# ZYNQ_PW.net
KiCad netlist of a schematic drawn in Altium Designer
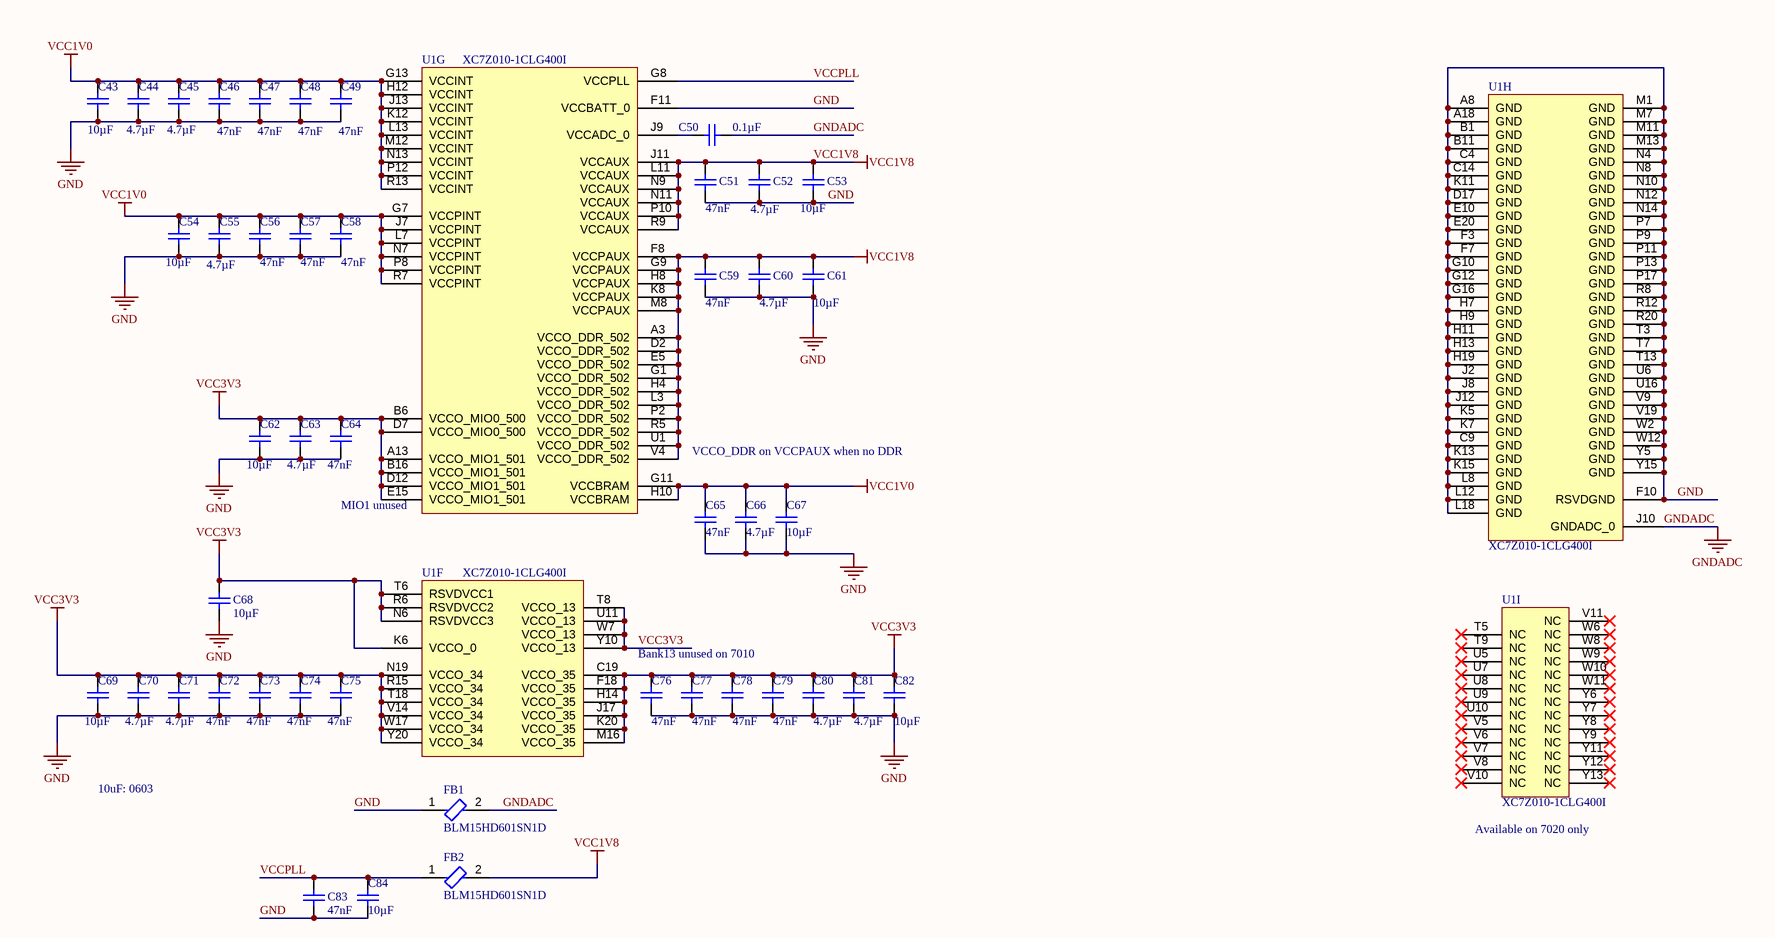
[diagram p0: ZYNQ_PW.SchDoc]

(export (version "E")
  (design (tool "Eeschema 10.0.6"))
  (components
    (comp (ref "C43")
      (value "10µF")
      (footprint "CAP0805i")
      (description "0805, 10uF, 10%, 25V, X7S")
      (fields
        (field (name "PART NUMBER") "GRT21BC71E106KE13L")
        (field (name "VOLTAGE") "25V")
        (field (name "CAPACITANCE") "10µF")
      )
      (libsource (lib "AmpherLib") (part "Cap_10uF_50V_X7S_0805"))
    )
    (comp (ref "C44")
      (value "4.7µF")
      (footprint "CAP0402i")
      (description "CAP CER 4.7UF 10V X5R 0402")
      (fields (field (name "PART NUMBER") "C1005X5R1A475K050BC") (field (name "TOLERANCE") "10%"))
      (libsource (lib "AmpherLib") (part "Cap_4.7uF_10V_10%_0402"))
    )
    (comp (ref "C45")
      (value "4.7µF")
      (footprint "CAP0402i")
      (description "CAP CER 4.7UF 10V X5R 0402")
      (fields
        (field (name "PART NUMBER") "C1005X5R1A475K050BC")
        (field (name "CAPACITANCE") "4.7µF")
        (field (name "TOLERANCE") "10%")
      )
      (libsource (lib "AmpherLib") (part "Cap_4.7uF_10V_10%_0402"))
    )
    (comp (ref "C46")
      (value "~")
      (footprint "CAP0201i")
      (description "0201, 47nF, 10%, 25V, X7R")
      (fields (field (name "CAPACITANCE") "47nF"))
      (libsource (lib "AmpherLib") (part "Cap_47nF_X7R_0201"))
    )
    (comp (ref "C47")
      (value "~")
      (footprint "CAP0201i")
      (description "0201, 47nF, 10%, 25V, X7R")
      (fields (field (name "CAPACITANCE") "47nF"))
      (libsource (lib "AmpherLib") (part "Cap_47nF_X7R_0201"))
    )
    (comp (ref "C48")
      (value "~")
      (footprint "CAP0201i")
      (description "0201, 47nF, 10%, 25V, X7R")
      (fields (field (name "CAPACITANCE") "47nF"))
      (libsource (lib "AmpherLib") (part "Cap_47nF_X7R_0201"))
    )
    (comp (ref "C49")
      (value "~")
      (footprint "CAP0201i")
      (description "0201, 47nF, 10%, 25V, X7R")
      (fields (field (name "CAPACITANCE") "47nF"))
      (libsource (lib "AmpherLib") (part "Cap_47nF_X7R_0201"))
    )
    (comp (ref "C50")
      (value "0.1µF")
      (footprint "CAP0402i")
      (description "0402, 0.1uF, 10%,  50V, X7R")
      (fields
        (field (name "PART NUMBER") "C1005X7R1H104K050BE")
        (field (name "VOLTAGE") "50V")
        (field (name "CAPACITANCE") "0.1µF")
      )
      (libsource (lib "AmpherLib") (part "Cap_0.1uF_50V_X7R_0402"))
    )
    (comp (ref "C51")
      (value "~")
      (footprint "CAP0201i")
      (description "0201, 47nF, 10%, 25V, X7R")
      (fields (field (name "CAPACITANCE") "47nF"))
      (libsource (lib "AmpherLib") (part "Cap_47nF_X7R_0201"))
    )
    (comp (ref "C52")
      (value "4.7µF")
      (footprint "CAP0402i")
      (description "CAP CER 4.7UF 10V X5R 0402")
      (fields
        (field (name "PART NUMBER") "C1005X5R1A475K050BC")
        (field (name "CAPACITANCE") "4.7µF")
        (field (name "TOLERANCE") "10%")
      )
      (libsource (lib "AmpherLib") (part "Cap_4.7uF_10V_10%_0402"))
    )
    (comp (ref "C53")
      (value "10µF")
      (footprint "CAP0805i")
      (description "0805, 10uF, 10%, 25V, X7S")
      (fields
        (field (name "PART NUMBER") "GRT21BC71E106KE13L")
        (field (name "VOLTAGE") "25V")
        (field (name "CAPACITANCE") "10µF")
      )
      (libsource (lib "AmpherLib") (part "Cap_10uF_50V_X7S_0805"))
    )
    (comp (ref "C54")
      (value "10µF")
      (footprint "CAP0805i")
      (description "0805, 10uF, 10%, 25V, X7S")
      (fields
        (field (name "PART NUMBER") "GRT21BC71E106KE13L")
        (field (name "VOLTAGE") "25V")
        (field (name "CAPACITANCE") "10µF")
      )
      (libsource (lib "AmpherLib") (part "Cap_10uF_50V_X7S_0805"))
    )
    (comp (ref "C55")
      (value "4.7µF")
      (footprint "CAP0402i")
      (description "CAP CER 4.7UF 10V X5R 0402")
      (fields
        (field (name "PART NUMBER") "C1005X5R1A475K050BC")
        (field (name "CAPACITANCE") "4.7µF")
        (field (name "TOLERANCE") "10%")
      )
      (libsource (lib "AmpherLib") (part "Cap_4.7uF_10V_10%_0402"))
    )
    (comp (ref "C56")
      (value "~")
      (footprint "CAP0201i")
      (description "0201, 47nF, 10%, 25V, X7R")
      (fields (field (name "CAPACITANCE") "47nF"))
      (libsource (lib "AmpherLib") (part "Cap_47nF_X7R_0201"))
    )
    (comp (ref "C57")
      (value "~")
      (footprint "CAP0201i")
      (description "0201, 47nF, 10%, 25V, X7R")
      (fields (field (name "CAPACITANCE") "47nF"))
      (libsource (lib "AmpherLib") (part "Cap_47nF_X7R_0201"))
    )
    (comp (ref "C58")
      (value "~")
      (footprint "CAP0201i")
      (description "0201, 47nF, 10%, 25V, X7R")
      (fields (field (name "CAPACITANCE") "47nF"))
      (libsource (lib "AmpherLib") (part "Cap_47nF_X7R_0201"))
    )
    (comp (ref "C59")
      (value "~")
      (footprint "CAP0201i")
      (description "0201, 47nF, 10%, 25V, X7R")
      (fields (field (name "CAPACITANCE") "47nF"))
      (libsource (lib "AmpherLib") (part "Cap_47nF_X7R_0201"))
    )
    (comp (ref "C60")
      (value "4.7µF")
      (footprint "CAP0402i")
      (description "CAP CER 4.7UF 10V X5R 0402")
      (fields
        (field (name "PART NUMBER") "C1005X5R1A475K050BC")
        (field (name "CAPACITANCE") "4.7µF")
        (field (name "TOLERANCE") "10%")
      )
      (libsource (lib "AmpherLib") (part "Cap_4.7uF_10V_10%_0402"))
    )
    (comp (ref "C61")
      (value "10µF")
      (footprint "CAP0805i")
      (description "0805, 10uF, 10%, 25V, X7S")
      (fields
        (field (name "PART NUMBER") "GRT21BC71E106KE13L")
        (field (name "VOLTAGE") "25V")
        (field (name "CAPACITANCE") "10µF")
      )
      (libsource (lib "AmpherLib") (part "Cap_10uF_50V_X7S_0805"))
    )
    (comp (ref "C62")
      (value "10µF")
      (footprint "CAP0805i")
      (description "0805, 10uF, 10%, 25V, X7S")
      (fields
        (field (name "PART NUMBER") "GRT21BC71E106KE13L")
        (field (name "VOLTAGE") "25V")
        (field (name "CAPACITANCE") "10µF")
      )
      (libsource (lib "AmpherLib") (part "Cap_10uF_50V_X7S_0805"))
    )
    (comp (ref "C63")
      (value "4.7µF")
      (footprint "CAP0402i")
      (description "CAP CER 4.7UF 10V X5R 0402")
      (fields (field (name "PART NUMBER") "C1005X5R1A475K050BC") (field (name "TOLERANCE") "10%"))
      (libsource (lib "AmpherLib") (part "Cap_4.7uF_10V_10%_0402"))
    )
    (comp (ref "C64")
      (value "~")
      (footprint "CAP0201i")
      (description "0201, 47nF, 10%, 25V, X7R")
      (fields (field (name "CAPACITANCE") "47nF"))
      (libsource (lib "AmpherLib") (part "Cap_47nF_X7R_0201"))
    )
    (comp (ref "C65")
      (value "~")
      (footprint "CAP0201i")
      (description "0201, 47nF, 10%, 25V, X7R")
      (fields (field (name "CAPACITANCE") "47nF"))
      (libsource (lib "AmpherLib") (part "Cap_47nF_X7R_0201"))
    )
    (comp (ref "C66")
      (value "4.7µF")
      (footprint "CAP0402i")
      (description "CAP CER 4.7UF 10V X5R 0402")
      (fields
        (field (name "PART NUMBER") "C1005X5R1A475K050BC")
        (field (name "CAPACITANCE") "4.7µF")
        (field (name "TOLERANCE") "10%")
      )
      (libsource (lib "AmpherLib") (part "Cap_4.7uF_10V_10%_0402"))
    )
    (comp (ref "C67")
      (value "10µF")
      (footprint "CAP0805i")
      (description "0805, 10uF, 10%, 25V, X7S")
      (fields (field (name "PART NUMBER") "GRT21BC71E106KE13L") (field (name "VOLTAGE") "25V"))
      (libsource (lib "AmpherLib") (part "Cap_10uF_50V_X7S_0805"))
    )
    (comp (ref "C68")
      (value "10µF")
      (footprint "CAP0805i")
      (description "0805, 10uF, 10%, 25V, X7S")
      (fields (field (name "PART NUMBER") "GRT21BC71E106KE13L") (field (name "VOLTAGE") "25V"))
      (libsource (lib "AmpherLib") (part "Cap_10uF_50V_X7S_0805"))
    )
    (comp (ref "C69")
      (value "10µF")
      (footprint "CAP0805i")
      (description "0805, 10uF, 10%, 25V, X7S")
      (fields (field (name "PART NUMBER") "GRT21BC71E106KE13L") (field (name "VOLTAGE") "25V"))
      (libsource (lib "AmpherLib") (part "Cap_10uF_50V_X7S_0805"))
    )
    (comp (ref "C70")
      (value "4.7µF")
      (footprint "CAP0402i")
      (description "CAP CER 4.7UF 10V X5R 0402")
      (fields
        (field (name "PART NUMBER") "C1005X5R1A475K050BC")
        (field (name "CAPACITANCE") "4.7µF")
        (field (name "TOLERANCE") "10%")
      )
      (libsource (lib "AmpherLib") (part "Cap_4.7uF_10V_10%_0402"))
    )
    (comp (ref "C71")
      (value "4.7µF")
      (footprint "CAP0402i")
      (description "CAP CER 4.7UF 10V X5R 0402")
      (fields
        (field (name "PART NUMBER") "C1005X5R1A475K050BC")
        (field (name "CAPACITANCE") "4.7µF")
        (field (name "TOLERANCE") "10%")
      )
      (libsource (lib "AmpherLib") (part "Cap_4.7uF_10V_10%_0402"))
    )
    (comp (ref "C72")
      (value "~")
      (footprint "CAP0201i")
      (description "0201, 47nF, 10%, 25V, X7R")
      (fields (field (name "CAPACITANCE") "47nF"))
      (libsource (lib "AmpherLib") (part "Cap_47nF_X7R_0201"))
    )
    (comp (ref "C73")
      (value "~")
      (footprint "CAP0201i")
      (description "0201, 47nF, 10%, 25V, X7R")
      (fields (field (name "CAPACITANCE") "47nF"))
      (libsource (lib "AmpherLib") (part "Cap_47nF_X7R_0201"))
    )
    (comp (ref "C74")
      (value "~")
      (footprint "CAP0201i")
      (description "0201, 47nF, 10%, 25V, X7R")
      (fields (field (name "CAPACITANCE") "47nF"))
      (libsource (lib "AmpherLib") (part "Cap_47nF_X7R_0201"))
    )
    (comp (ref "C75")
      (value "~")
      (footprint "CAP0201i")
      (description "0201, 47nF, 10%, 25V, X7R")
      (fields (field (name "CAPACITANCE") "47nF"))
      (libsource (lib "AmpherLib") (part "Cap_47nF_X7R_0201"))
    )
    (comp (ref "C76")
      (value "~")
      (footprint "CAP0201i")
      (description "0201, 47nF, 10%, 25V, X7R")
      (fields (field (name "CAPACITANCE") "47nF"))
      (libsource (lib "AmpherLib") (part "Cap_47nF_X7R_0201"))
    )
    (comp (ref "C77")
      (value "~")
      (footprint "CAP0201i")
      (description "0201, 47nF, 10%, 25V, X7R")
      (fields (field (name "CAPACITANCE") "47nF"))
      (libsource (lib "AmpherLib") (part "Cap_47nF_X7R_0201"))
    )
    (comp (ref "C78")
      (value "~")
      (footprint "CAP0201i")
      (description "0201, 47nF, 10%, 25V, X7R")
      (fields (field (name "CAPACITANCE") "47nF"))
      (libsource (lib "AmpherLib") (part "Cap_47nF_X7R_0201"))
    )
    (comp (ref "C79")
      (value "~")
      (footprint "CAP0201i")
      (description "0201, 47nF, 10%, 25V, X7R")
      (fields (field (name "CAPACITANCE") "47nF"))
      (libsource (lib "AmpherLib") (part "Cap_47nF_X7R_0201"))
    )
    (comp (ref "C80")
      (value "4.7µF")
      (footprint "CAP0402i")
      (description "CAP CER 4.7UF 10V X5R 0402")
      (fields
        (field (name "PART NUMBER") "C1005X5R1A475K050BC")
        (field (name "CAPACITANCE") "4.7µF")
        (field (name "TOLERANCE") "10%")
      )
      (libsource (lib "AmpherLib") (part "Cap_4.7uF_10V_10%_0402"))
    )
    (comp (ref "C81")
      (value "4.7µF")
      (footprint "CAP0402i")
      (description "CAP CER 4.7UF 10V X5R 0402")
      (fields (field (name "PART NUMBER") "C1005X5R1A475K050BC") (field (name "TOLERANCE") "10%"))
      (libsource (lib "AmpherLib") (part "Cap_4.7uF_10V_10%_0402"))
    )
    (comp (ref "C82")
      (value "10µF")
      (footprint "CAP0805i")
      (description "0805, 10uF, 10%, 25V, X7S")
      (fields (field (name "PART NUMBER") "GRT21BC71E106KE13L") (field (name "VOLTAGE") "25V"))
      (libsource (lib "AmpherLib") (part "Cap_10uF_50V_X7S_0805"))
    )
    (comp (ref "C83")
      (value "~")
      (footprint "CAP0201i")
      (description "0201, 47nF, 10%, 25V, X7R")
      (fields (field (name "CAPACITANCE") "47nF"))
      (libsource (lib "AmpherLib") (part "Cap_47nF_X7R_0201"))
    )
    (comp (ref "C84")
      (value "10µF")
      (footprint "CAP0805i")
      (description "0805, 10uF, 10%, 25V, X7S")
      (fields (field (name "PART NUMBER") "GRT21BC71E106KE13L") (field (name "VOLTAGE") "25V"))
      (libsource (lib "AmpherLib") (part "Cap_10uF_50V_X7S_0805"))
    )
    (comp (ref "FB1")
      (value "BLM15HD601SN1D")
      (footprint "FP-BLM15-0_05-MFG")
      (description "Chip Ferrite Bead, 0402, 600Ω @ 100MHz, 0.85Ω, 25%, 300mA")
      (fields (field (name "TOLERANCE") "25%"))
      (libsource (lib "CCZynq") (part "CMP-0686-00273-4"))
    )
    (comp (ref "FB2")
      (value "BLM15HD601SN1D")
      (footprint "FP-BLM15-0_05-MFG")
      (description "Chip Ferrite Bead, 0402, 600Ω @ 100MHz, 0.85Ω, 25%, 300mA")
      (fields (field (name "TOLERANCE") "25%"))
      (libsource (lib "CCZynq") (part "CMP-0686-00273-4"))
    )
    (comp (ref "U1")
      (value "XC7Z010-1CLG400I")
      (footprint "CLG400")
      (fields (field (name "GENERIC PART NUMBER") "XC7Z010") (field (name "MANUFACTURER") "Xilinx"))
      (libsource (lib "CCZynq") (part "XC7Z010-1CLG400I"))
    )
  )
  (nets
    (net (code "1") (name "/VCCPLL") (class "Default")
      (node (ref "C83") (pin "2") (pinfunction "2_2") (pintype "passive"))
      (node (ref "C84") (pin "1") (pinfunction "1_1") (pintype "passive"))
      (node (ref "FB2") (pin "1") (pinfunction "1_1") (pintype "passive"))
      (node (ref "U1") (pin "G8") (pinfunction "VCCPLL_G8") (pintype "power_in"))
    )
    (net (code "2") (name "GND") (class "Default")
      (node (ref "C43") (pin "2") (pinfunction "2_2") (pintype "passive"))
      (node (ref "C44") (pin "2") (pinfunction "2_2") (pintype "passive"))
      (node (ref "C45") (pin "2") (pinfunction "2_2") (pintype "passive"))
      (node (ref "C46") (pin "2") (pinfunction "2_2") (pintype "passive"))
      (node (ref "C47") (pin "2") (pinfunction "2_2") (pintype "passive"))
      (node (ref "C48") (pin "2") (pinfunction "2_2") (pintype "passive"))
      (node (ref "C49") (pin "2") (pinfunction "2_2") (pintype "passive"))
      (node (ref "C51") (pin "1") (pinfunction "1_1") (pintype "passive"))
      (node (ref "C52") (pin "1") (pinfunction "1_1") (pintype "passive"))
      (node (ref "C53") (pin "1") (pinfunction "1_1") (pintype "passive"))
      (node (ref "C54") (pin "2") (pinfunction "2_2") (pintype "passive"))
      (node (ref "C55") (pin "2") (pinfunction "2_2") (pintype "passive"))
      (node (ref "C56") (pin "2") (pinfunction "2_2") (pintype "passive"))
      (node (ref "C57") (pin "2") (pinfunction "2_2") (pintype "passive"))
      (node (ref "C58") (pin "2") (pinfunction "2_2") (pintype "passive"))
      (node (ref "C59") (pin "1") (pinfunction "1_1") (pintype "passive"))
      (node (ref "C60") (pin "1") (pinfunction "1_1") (pintype "passive"))
      (node (ref "C61") (pin "1") (pinfunction "1_1") (pintype "passive"))
      (node (ref "C62") (pin "2") (pinfunction "2_2") (pintype "passive"))
      (node (ref "C63") (pin "2") (pinfunction "2_2") (pintype "passive"))
      (node (ref "C64") (pin "2") (pinfunction "2_2") (pintype "passive"))
      (node (ref "C65") (pin "1") (pinfunction "1_1") (pintype "passive"))
      (node (ref "C66") (pin "1") (pinfunction "1_1") (pintype "passive"))
      (node (ref "C67") (pin "1") (pinfunction "1_1") (pintype "passive"))
      (node (ref "C68") (pin "1") (pinfunction "1_1") (pintype "passive"))
      (node (ref "C69") (pin "2") (pinfunction "2_2") (pintype "passive"))
      (node (ref "C70") (pin "2") (pinfunction "2_2") (pintype "passive"))
      (node (ref "C71") (pin "2") (pinfunction "2_2") (pintype "passive"))
      (node (ref "C72") (pin "2") (pinfunction "2_2") (pintype "passive"))
      (node (ref "C73") (pin "2") (pinfunction "2_2") (pintype "passive"))
      (node (ref "C74") (pin "2") (pinfunction "2_2") (pintype "passive"))
      (node (ref "C75") (pin "2") (pinfunction "2_2") (pintype "passive"))
      (node (ref "C76") (pin "2") (pinfunction "2_2") (pintype "passive"))
      (node (ref "C77") (pin "2") (pinfunction "2_2") (pintype "passive"))
      (node (ref "C78") (pin "2") (pinfunction "2_2") (pintype "passive"))
      (node (ref "C79") (pin "2") (pinfunction "2_2") (pintype "passive"))
      (node (ref "C80") (pin "2") (pinfunction "2_2") (pintype "passive"))
      (node (ref "C81") (pin "2") (pinfunction "2_2") (pintype "passive"))
      (node (ref "C82") (pin "2") (pinfunction "2_2") (pintype "passive"))
      (node (ref "C83") (pin "1") (pinfunction "1_1") (pintype "passive"))
      (node (ref "C84") (pin "2") (pinfunction "2_2") (pintype "passive"))
      (node (ref "FB1") (pin "1") (pinfunction "1_1") (pintype "passive"))
      (node (ref "U1") (pin "A18") (pinfunction "GND_A18") (pintype "power_in"))
      (node (ref "U1") (pin "A8") (pinfunction "GND_A8") (pintype "power_in"))
      (node (ref "U1") (pin "B1") (pinfunction "GND_B1") (pintype "power_in"))
      (node (ref "U1") (pin "B11") (pinfunction "GND_B11") (pintype "power_in"))
      (node (ref "U1") (pin "C14") (pinfunction "GND_C14") (pintype "power_in"))
      (node (ref "U1") (pin "C4") (pinfunction "GND_C4") (pintype "power_in"))
      (node (ref "U1") (pin "C9") (pinfunction "GND_C9") (pintype "power_in"))
      (node (ref "U1") (pin "D17") (pinfunction "GND_D17") (pintype "power_in"))
      (node (ref "U1") (pin "E10") (pinfunction "GND_E10") (pintype "power_in"))
      (node (ref "U1") (pin "E20") (pinfunction "GND_E20") (pintype "power_in"))
      (node (ref "U1") (pin "F10") (pinfunction "RSVDGND_F10") (pintype "power_in"))
      (node (ref "U1") (pin "F11") (pinfunction "VCCBATT_0_F11") (pintype "power_in"))
      (node (ref "U1") (pin "F3") (pinfunction "GND_F3") (pintype "power_in"))
      (node (ref "U1") (pin "F7") (pinfunction "GND_F7") (pintype "power_in"))
      (node (ref "U1") (pin "G10") (pinfunction "GND_G10") (pintype "power_in"))
      (node (ref "U1") (pin "G12") (pinfunction "GND_G12") (pintype "power_in"))
      (node (ref "U1") (pin "G16") (pinfunction "GND_G16") (pintype "power_in"))
      (node (ref "U1") (pin "H11") (pinfunction "GND_H11") (pintype "power_in"))
      (node (ref "U1") (pin "H13") (pinfunction "GND_H13") (pintype "power_in"))
      (node (ref "U1") (pin "H19") (pinfunction "GND_H19") (pintype "power_in"))
      (node (ref "U1") (pin "H7") (pinfunction "GND_H7") (pintype "power_in"))
      (node (ref "U1") (pin "H9") (pinfunction "GND_H9") (pintype "power_in"))
      (node (ref "U1") (pin "J12") (pinfunction "GND_J12") (pintype "power_in"))
      (node (ref "U1") (pin "J2") (pinfunction "GND_J2") (pintype "power_in"))
      (node (ref "U1") (pin "J8") (pinfunction "GND_J8") (pintype "power_in"))
      (node (ref "U1") (pin "K11") (pinfunction "GND_K11") (pintype "power_in"))
      (node (ref "U1") (pin "K13") (pinfunction "GND_K13") (pintype "power_in"))
      (node (ref "U1") (pin "K15") (pinfunction "GND_K15") (pintype "power_in"))
      (node (ref "U1") (pin "K5") (pinfunction "GND_K5") (pintype "power_in"))
      (node (ref "U1") (pin "K7") (pinfunction "GND_K7") (pintype "power_in"))
      (node (ref "U1") (pin "L12") (pinfunction "GND_L12") (pintype "power_in"))
      (node (ref "U1") (pin "L18") (pinfunction "GND_L18") (pintype "power_in"))
      (node (ref "U1") (pin "L8") (pinfunction "GND_L8") (pintype "power_in"))
      (node (ref "U1") (pin "M1") (pinfunction "GND_M1") (pintype "power_in"))
      (node (ref "U1") (pin "M11") (pinfunction "GND_M11") (pintype "power_in"))
      (node (ref "U1") (pin "M13") (pinfunction "GND_M13") (pintype "power_in"))
      (node (ref "U1") (pin "M7") (pinfunction "GND_M7") (pintype "power_in"))
      (node (ref "U1") (pin "N10") (pinfunction "GND_N10") (pintype "power_in"))
      (node (ref "U1") (pin "N12") (pinfunction "GND_N12") (pintype "power_in"))
      (node (ref "U1") (pin "N14") (pinfunction "GND_N14") (pintype "power_in"))
      (node (ref "U1") (pin "N4") (pinfunction "GND_N4") (pintype "power_in"))
      (node (ref "U1") (pin "N8") (pinfunction "GND_N8") (pintype "power_in"))
      (node (ref "U1") (pin "P11") (pinfunction "GND_P11") (pintype "power_in"))
      (node (ref "U1") (pin "P13") (pinfunction "GND_P13") (pintype "power_in"))
      (node (ref "U1") (pin "P17") (pinfunction "GND_P17") (pintype "power_in"))
      (node (ref "U1") (pin "P7") (pinfunction "GND_P7") (pintype "power_in"))
      (node (ref "U1") (pin "P9") (pinfunction "GND_P9") (pintype "power_in"))
      (node (ref "U1") (pin "R12") (pinfunction "GND_R12") (pintype "power_in"))
      (node (ref "U1") (pin "R20") (pinfunction "GND_R20") (pintype "power_in"))
      (node (ref "U1") (pin "R8") (pinfunction "GND_R8") (pintype "power_in"))
      (node (ref "U1") (pin "T13") (pinfunction "GND_T13") (pintype "power_in"))
      (node (ref "U1") (pin "T3") (pinfunction "GND_T3") (pintype "power_in"))
      (node (ref "U1") (pin "T7") (pinfunction "GND_T7") (pintype "power_in"))
      (node (ref "U1") (pin "U16") (pinfunction "GND_U16") (pintype "power_in"))
      (node (ref "U1") (pin "U6") (pinfunction "GND_U6") (pintype "power_in"))
      (node (ref "U1") (pin "V19") (pinfunction "GND_V19") (pintype "power_in"))
      (node (ref "U1") (pin "V9") (pinfunction "GND_V9") (pintype "power_in"))
      (node (ref "U1") (pin "W12") (pinfunction "GND_W12") (pintype "power_in"))
      (node (ref "U1") (pin "W2") (pinfunction "GND_W2") (pintype "power_in"))
      (node (ref "U1") (pin "Y15") (pinfunction "GND_Y15") (pintype "power_in"))
      (node (ref "U1") (pin "Y5") (pinfunction "GND_Y5") (pintype "power_in"))
    )
    (net (code "3") (name "GNDADC") (class "Default")
      (node (ref "C50") (pin "2") (pinfunction "2_2") (pintype "passive"))
      (node (ref "FB1") (pin "2") (pinfunction "2_2") (pintype "passive"))
      (node (ref "U1") (pin "J10") (pinfunction "GNDADC_0_J10") (pintype "power_in"))
    )
    (net (code "4") (name "Net-(U1G-VCCADC_0)") (class "Default")
      (node (ref "C50") (pin "1") (pinfunction "1_1") (pintype "passive"))
      (node (ref "U1") (pin "J9") (pinfunction "VCCADC_0_J9") (pintype "power_in"))
    )
    (net (code "5") (name "VCC1V0") (class "Default")
      (node (ref "C43") (pin "1") (pinfunction "1_1") (pintype "passive"))
      (node (ref "C44") (pin "1") (pinfunction "1_1") (pintype "passive"))
      (node (ref "C45") (pin "1") (pinfunction "1_1") (pintype "passive"))
      (node (ref "C46") (pin "1") (pinfunction "1_1") (pintype "passive"))
      (node (ref "C47") (pin "1") (pinfunction "1_1") (pintype "passive"))
      (node (ref "C48") (pin "1") (pinfunction "1_1") (pintype "passive"))
      (node (ref "C49") (pin "1") (pinfunction "1_1") (pintype "passive"))
      (node (ref "C54") (pin "1") (pinfunction "1_1") (pintype "passive"))
      (node (ref "C55") (pin "1") (pinfunction "1_1") (pintype "passive"))
      (node (ref "C56") (pin "1") (pinfunction "1_1") (pintype "passive"))
      (node (ref "C57") (pin "1") (pinfunction "1_1") (pintype "passive"))
      (node (ref "C58") (pin "1") (pinfunction "1_1") (pintype "passive"))
      (node (ref "C65") (pin "2") (pinfunction "2_2") (pintype "passive"))
      (node (ref "C66") (pin "2") (pinfunction "2_2") (pintype "passive"))
      (node (ref "C67") (pin "2") (pinfunction "2_2") (pintype "passive"))
      (node (ref "U1") (pin "G11") (pinfunction "VCCBRAM_G11") (pintype "power_in"))
      (node (ref "U1") (pin "G13") (pinfunction "VCCINT_G13") (pintype "power_in"))
      (node (ref "U1") (pin "G7") (pinfunction "VCCPINT_G7") (pintype "power_in"))
      (node (ref "U1") (pin "H10") (pinfunction "VCCBRAM_H10") (pintype "power_in"))
      (node (ref "U1") (pin "H12") (pinfunction "VCCINT_H12") (pintype "power_in"))
      (node (ref "U1") (pin "J13") (pinfunction "VCCINT_J13") (pintype "power_in"))
      (node (ref "U1") (pin "J7") (pinfunction "VCCPINT_J7") (pintype "power_in"))
      (node (ref "U1") (pin "K12") (pinfunction "VCCINT_K12") (pintype "power_in"))
      (node (ref "U1") (pin "L13") (pinfunction "VCCINT_L13") (pintype "power_in"))
      (node (ref "U1") (pin "L7") (pinfunction "VCCPINT_L7") (pintype "power_in"))
      (node (ref "U1") (pin "M12") (pinfunction "VCCINT_M12") (pintype "power_in"))
      (node (ref "U1") (pin "N13") (pinfunction "VCCINT_N13") (pintype "power_in"))
      (node (ref "U1") (pin "N7") (pinfunction "VCCPINT_N7") (pintype "power_in"))
      (node (ref "U1") (pin "P12") (pinfunction "VCCINT_P12") (pintype "power_in"))
      (node (ref "U1") (pin "P8") (pinfunction "VCCPINT_P8") (pintype "power_in"))
      (node (ref "U1") (pin "R13") (pinfunction "VCCINT_R13") (pintype "power_in"))
      (node (ref "U1") (pin "R7") (pinfunction "VCCPINT_R7") (pintype "power_in"))
    )
    (net (code "6") (name "VCC1V8") (class "Default")
      (node (ref "C51") (pin "2") (pinfunction "2_2") (pintype "passive"))
      (node (ref "C52") (pin "2") (pinfunction "2_2") (pintype "passive"))
      (node (ref "C53") (pin "2") (pinfunction "2_2") (pintype "passive"))
      (node (ref "C59") (pin "2") (pinfunction "2_2") (pintype "passive"))
      (node (ref "C60") (pin "2") (pinfunction "2_2") (pintype "passive"))
      (node (ref "C61") (pin "2") (pinfunction "2_2") (pintype "passive"))
      (node (ref "FB2") (pin "2") (pinfunction "2_2") (pintype "passive"))
      (node (ref "U1") (pin "A3") (pinfunction "VCCO_DDR_502_A3") (pintype "power_in"))
      (node (ref "U1") (pin "D2") (pinfunction "VCCO_DDR_502_D2") (pintype "power_in"))
      (node (ref "U1") (pin "E5") (pinfunction "VCCO_DDR_502_E5") (pintype "power_in"))
      (node (ref "U1") (pin "F8") (pinfunction "VCCPAUX_F8") (pintype "power_in"))
      (node (ref "U1") (pin "G1") (pinfunction "VCCO_DDR_502_G1") (pintype "power_in"))
      (node (ref "U1") (pin "G9") (pinfunction "VCCPAUX_G9") (pintype "power_in"))
      (node (ref "U1") (pin "H4") (pinfunction "VCCO_DDR_502_H4") (pintype "power_in"))
      (node (ref "U1") (pin "H8") (pinfunction "VCCPAUX_H8") (pintype "power_in"))
      (node (ref "U1") (pin "J11") (pinfunction "VCCAUX_J11") (pintype "power_in"))
      (node (ref "U1") (pin "K8") (pinfunction "VCCPAUX_K8") (pintype "power_in"))
      (node (ref "U1") (pin "L11") (pinfunction "VCCAUX_L11") (pintype "power_in"))
      (node (ref "U1") (pin "L3") (pinfunction "VCCO_DDR_502_L3") (pintype "power_in"))
      (node (ref "U1") (pin "M8") (pinfunction "VCCPAUX_M8") (pintype "power_in"))
      (node (ref "U1") (pin "N11") (pinfunction "VCCAUX_N11") (pintype "power_in"))
      (node (ref "U1") (pin "N9") (pinfunction "VCCAUX_N9") (pintype "power_in"))
      (node (ref "U1") (pin "P10") (pinfunction "VCCAUX_P10") (pintype "power_in"))
      (node (ref "U1") (pin "P2") (pinfunction "VCCO_DDR_502_P2") (pintype "power_in"))
      (node (ref "U1") (pin "R5") (pinfunction "VCCO_DDR_502_R5") (pintype "power_in"))
      (node (ref "U1") (pin "R9") (pinfunction "VCCAUX_R9") (pintype "power_in"))
      (node (ref "U1") (pin "U1") (pinfunction "VCCO_DDR_502_U1") (pintype "power_in"))
      (node (ref "U1") (pin "V4") (pinfunction "VCCO_DDR_502_V4") (pintype "power_in"))
    )
    (net (code "7") (name "VCC3V3") (class "Default")
      (node (ref "C62") (pin "1") (pinfunction "1_1") (pintype "passive"))
      (node (ref "C63") (pin "1") (pinfunction "1_1") (pintype "passive"))
      (node (ref "C64") (pin "1") (pinfunction "1_1") (pintype "passive"))
      (node (ref "C68") (pin "2") (pinfunction "2_2") (pintype "passive"))
      (node (ref "C69") (pin "1") (pinfunction "1_1") (pintype "passive"))
      (node (ref "C70") (pin "1") (pinfunction "1_1") (pintype "passive"))
      (node (ref "C71") (pin "1") (pinfunction "1_1") (pintype "passive"))
      (node (ref "C72") (pin "1") (pinfunction "1_1") (pintype "passive"))
      (node (ref "C73") (pin "1") (pinfunction "1_1") (pintype "passive"))
      (node (ref "C74") (pin "1") (pinfunction "1_1") (pintype "passive"))
      (node (ref "C75") (pin "1") (pinfunction "1_1") (pintype "passive"))
      (node (ref "C76") (pin "1") (pinfunction "1_1") (pintype "passive"))
      (node (ref "C77") (pin "1") (pinfunction "1_1") (pintype "passive"))
      (node (ref "C78") (pin "1") (pinfunction "1_1") (pintype "passive"))
      (node (ref "C79") (pin "1") (pinfunction "1_1") (pintype "passive"))
      (node (ref "C80") (pin "1") (pinfunction "1_1") (pintype "passive"))
      (node (ref "C81") (pin "1") (pinfunction "1_1") (pintype "passive"))
      (node (ref "C82") (pin "1") (pinfunction "1_1") (pintype "passive"))
      (node (ref "U1") (pin "A13") (pinfunction "VCCO_MIO1_501_A13") (pintype "power_in"))
      (node (ref "U1") (pin "B16") (pinfunction "VCCO_MIO1_501_B16") (pintype "power_in"))
      (node (ref "U1") (pin "B6") (pinfunction "VCCO_MIO0_500_B6") (pintype "power_in"))
      (node (ref "U1") (pin "C19") (pinfunction "VCCO_35_C19") (pintype "power_in"))
      (node (ref "U1") (pin "D12") (pinfunction "VCCO_MIO1_501_D12") (pintype "power_in"))
      (node (ref "U1") (pin "D7") (pinfunction "VCCO_MIO0_500_D7") (pintype "power_in"))
      (node (ref "U1") (pin "E15") (pinfunction "VCCO_MIO1_501_E15") (pintype "power_in"))
      (node (ref "U1") (pin "F18") (pinfunction "VCCO_35_F18") (pintype "power_in"))
      (node (ref "U1") (pin "H14") (pinfunction "VCCO_35_H14") (pintype "power_in"))
      (node (ref "U1") (pin "J17") (pinfunction "VCCO_35_J17") (pintype "power_in"))
      (node (ref "U1") (pin "K20") (pinfunction "VCCO_35_K20") (pintype "power_in"))
      (node (ref "U1") (pin "K6") (pinfunction "VCCO_0_K6") (pintype "power_in"))
      (node (ref "U1") (pin "M16") (pinfunction "VCCO_35_M16") (pintype "power_in"))
      (node (ref "U1") (pin "N19") (pinfunction "VCCO_34_N19") (pintype "power_in"))
      (node (ref "U1") (pin "N6") (pinfunction "RSVDVCC3_N6") (pintype "power_in"))
      (node (ref "U1") (pin "R15") (pinfunction "VCCO_34_R15") (pintype "power_in"))
      (node (ref "U1") (pin "R6") (pinfunction "RSVDVCC2_R6") (pintype "power_in"))
      (node (ref "U1") (pin "T18") (pinfunction "VCCO_34_T18") (pintype "power_in"))
      (node (ref "U1") (pin "T6") (pinfunction "RSVDVCC1_T6") (pintype "power_in"))
      (node (ref "U1") (pin "T8") (pinfunction "VCCO_13_T8") (pintype "power_in"))
      (node (ref "U1") (pin "U11") (pinfunction "VCCO_13_U11") (pintype "power_in"))
      (node (ref "U1") (pin "V14") (pinfunction "VCCO_34_V14") (pintype "power_in"))
      (node (ref "U1") (pin "W17") (pinfunction "VCCO_34_W17") (pintype "power_in"))
      (node (ref "U1") (pin "W7") (pinfunction "VCCO_13_W7") (pintype "power_in"))
      (node (ref "U1") (pin "Y10") (pinfunction "VCCO_13_Y10") (pintype "power_in"))
      (node (ref "U1") (pin "Y20") (pinfunction "VCCO_34_Y20") (pintype "power_in"))
    )
    (net (code "8") (name "unconnected-(U1I-NC-PadT5)") (class "Default")
      (node (ref "U1") (pin "T5") (pinfunction "NC_T5") (pintype "passive+no_connect"))
    )
    (net (code "9") (name "unconnected-(U1I-NC-PadT9)") (class "Default")
      (node (ref "U1") (pin "T9") (pinfunction "NC_T9") (pintype "passive+no_connect"))
    )
    (net (code "10") (name "unconnected-(U1I-NC-PadU5)") (class "Default")
      (node (ref "U1") (pin "U5") (pinfunction "NC_U5") (pintype "passive+no_connect"))
    )
    (net (code "11") (name "unconnected-(U1I-NC-PadU7)") (class "Default")
      (node (ref "U1") (pin "U7") (pinfunction "NC_U7") (pintype "passive+no_connect"))
    )
    (net (code "12") (name "unconnected-(U1I-NC-PadU8)") (class "Default")
      (node (ref "U1") (pin "U8") (pinfunction "NC_U8") (pintype "passive+no_connect"))
    )
    (net (code "13") (name "unconnected-(U1I-NC-PadU9)") (class "Default")
      (node (ref "U1") (pin "U9") (pinfunction "NC_U9") (pintype "passive+no_connect"))
    )
    (net (code "14") (name "unconnected-(U1I-NC-PadU10)") (class "Default")
      (node (ref "U1") (pin "U10") (pinfunction "NC_U10") (pintype "passive+no_connect"))
    )
    (net (code "15") (name "unconnected-(U1I-NC-PadV5)") (class "Default")
      (node (ref "U1") (pin "V5") (pinfunction "NC_V5") (pintype "passive+no_connect"))
    )
    (net (code "16") (name "unconnected-(U1I-NC-PadV6)") (class "Default")
      (node (ref "U1") (pin "V6") (pinfunction "NC_V6") (pintype "passive+no_connect"))
    )
    (net (code "17") (name "unconnected-(U1I-NC-PadV7)") (class "Default")
      (node (ref "U1") (pin "V7") (pinfunction "NC_V7") (pintype "passive+no_connect"))
    )
    (net (code "18") (name "unconnected-(U1I-NC-PadV8)") (class "Default")
      (node (ref "U1") (pin "V8") (pinfunction "NC_V8") (pintype "passive+no_connect"))
    )
    (net (code "19") (name "unconnected-(U1I-NC-PadV10)") (class "Default")
      (node (ref "U1") (pin "V10") (pinfunction "NC_V10") (pintype "passive+no_connect"))
    )
    (net (code "20") (name "unconnected-(U1I-NC-PadV11)") (class "Default")
      (node (ref "U1") (pin "V11") (pinfunction "NC_V11") (pintype "passive+no_connect"))
    )
    (net (code "21") (name "unconnected-(U1I-NC-PadW6)") (class "Default")
      (node (ref "U1") (pin "W6") (pinfunction "NC_W6") (pintype "passive+no_connect"))
    )
    (net (code "22") (name "unconnected-(U1I-NC-PadW8)") (class "Default")
      (node (ref "U1") (pin "W8") (pinfunction "NC_W8") (pintype "passive+no_connect"))
    )
    (net (code "23") (name "unconnected-(U1I-NC-PadW9)") (class "Default")
      (node (ref "U1") (pin "W9") (pinfunction "NC_W9") (pintype "passive+no_connect"))
    )
    (net (code "24") (name "unconnected-(U1I-NC-PadW10)") (class "Default")
      (node (ref "U1") (pin "W10") (pinfunction "NC_W10") (pintype "passive+no_connect"))
    )
    (net (code "25") (name "unconnected-(U1I-NC-PadW11)") (class "Default")
      (node (ref "U1") (pin "W11") (pinfunction "NC_W11") (pintype "passive+no_connect"))
    )
    (net (code "26") (name "unconnected-(U1I-NC-PadY6)") (class "Default")
      (node (ref "U1") (pin "Y6") (pinfunction "NC_Y6") (pintype "passive+no_connect"))
    )
    (net (code "27") (name "unconnected-(U1I-NC-PadY7)") (class "Default")
      (node (ref "U1") (pin "Y7") (pinfunction "NC_Y7") (pintype "passive+no_connect"))
    )
    (net (code "28") (name "unconnected-(U1I-NC-PadY8)") (class "Default")
      (node (ref "U1") (pin "Y8") (pinfunction "NC_Y8") (pintype "passive+no_connect"))
    )
    (net (code "29") (name "unconnected-(U1I-NC-PadY9)") (class "Default")
      (node (ref "U1") (pin "Y9") (pinfunction "NC_Y9") (pintype "passive+no_connect"))
    )
    (net (code "30") (name "unconnected-(U1I-NC-PadY11)") (class "Default")
      (node (ref "U1") (pin "Y11") (pinfunction "NC_Y11") (pintype "passive+no_connect"))
    )
    (net (code "31") (name "unconnected-(U1I-NC-PadY12)") (class "Default")
      (node (ref "U1") (pin "Y12") (pinfunction "NC_Y12") (pintype "passive+no_connect"))
    )
    (net (code "32") (name "unconnected-(U1I-NC-PadY13)") (class "Default")
      (node (ref "U1") (pin "Y13") (pinfunction "NC_Y13") (pintype "passive+no_connect"))
    )
  )
)
